# FPGA_Clocks.net
KiCad netlist of a schematic drawn in Altium Designer
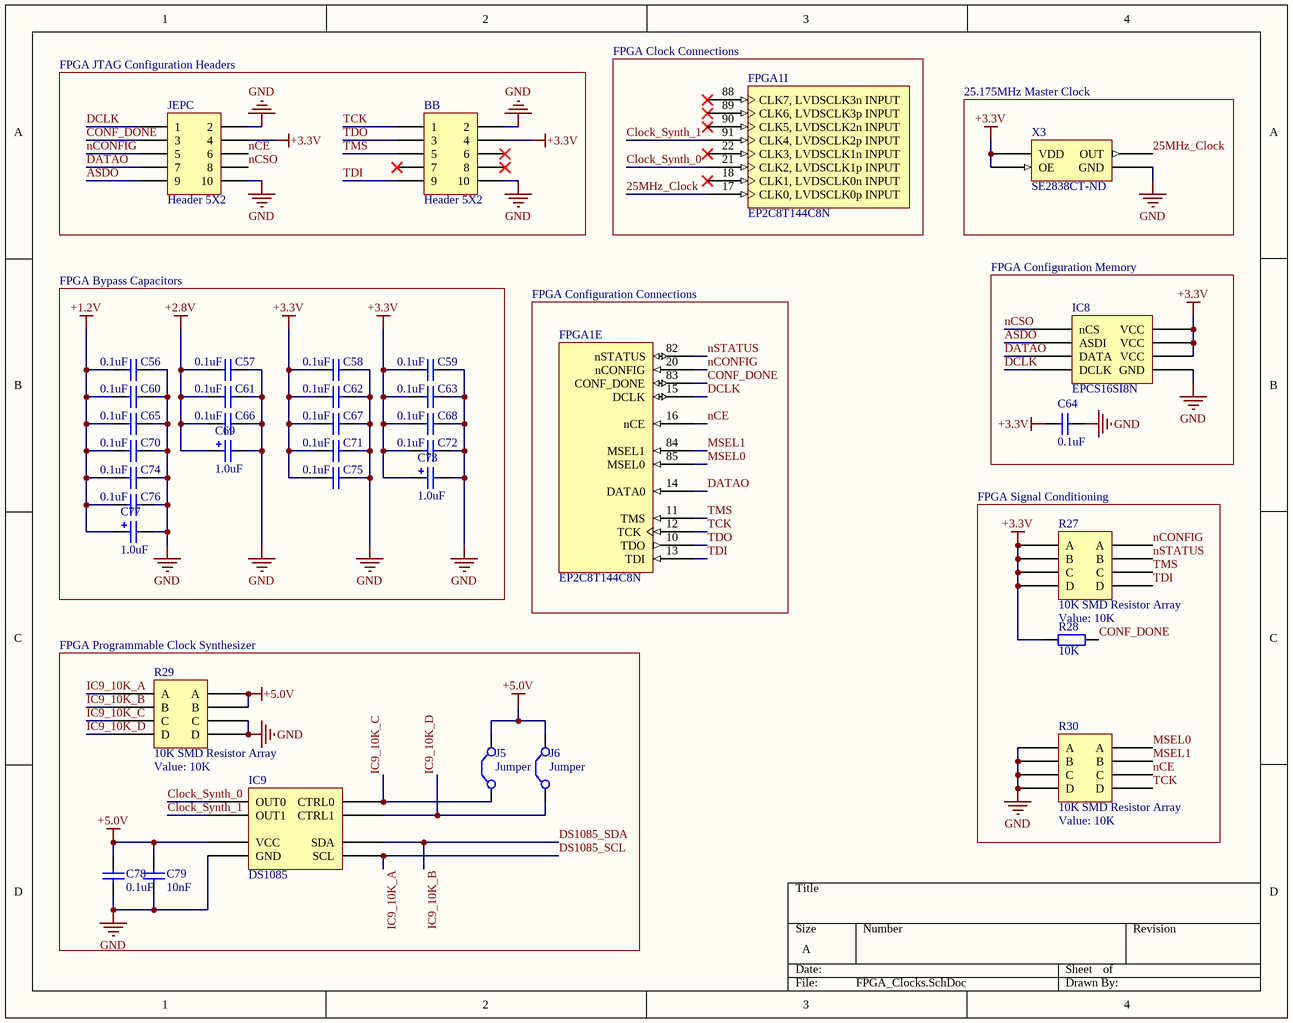
[diagram p0: FPGA_Clocks.SchDoc]

(export (version "E")
  (design (tool "Eeschema 10.0.6"))
  (components
    (comp (ref "BB")
      (value "Header 5X2")
      (footprint "HDR2X5")
      (description "Header, 5-Pin, Dual row")
      (fields (field (name "PUBLISHER") "Altium Limited"))
      (libsource (lib "Miscellaneous Connectors") (part "Header 5X2"))
    )
    (comp (ref "C56")
      (value "0.1uF")
      (footprint "SMD 1206")
      (description "Capacitor")
      (fields (field (name "Comment") "0.1uF SMD 1206"))
      (libsource (lib "Miscellaneous Devices") (part "Cap"))
    )
    (comp (ref "C57")
      (value "0.1uF")
      (footprint "SMD 1206")
      (description "Capacitor")
      (fields (field (name "Comment") "0.1uF SMD 1206"))
      (libsource (lib "Miscellaneous Devices") (part "Cap"))
    )
    (comp (ref "C58")
      (value "0.1uF")
      (footprint "SMD 1206")
      (description "Capacitor")
      (fields (field (name "Comment") "0.1uF SMD 1206"))
      (libsource (lib "Miscellaneous Devices") (part "Cap"))
    )
    (comp (ref "C59")
      (value "0.1uF")
      (footprint "SMD 1206")
      (description "Capacitor")
      (fields (field (name "Comment") "0.1uF SMD 1206"))
      (libsource (lib "Miscellaneous Devices") (part "Cap"))
    )
    (comp (ref "C60")
      (value "0.1uF")
      (footprint "SMD 1206")
      (description "Capacitor")
      (fields (field (name "Comment") "0.1uF SMD 1206"))
      (libsource (lib "Miscellaneous Devices") (part "Cap"))
    )
    (comp (ref "C61")
      (value "0.1uF")
      (footprint "SMD 1206")
      (description "Capacitor")
      (fields (field (name "Comment") "0.1uF SMD 1206"))
      (libsource (lib "Miscellaneous Devices") (part "Cap"))
    )
    (comp (ref "C62")
      (value "0.1uF")
      (footprint "SMD 1206")
      (description "Capacitor")
      (fields (field (name "Comment") "0.1uF SMD 1206"))
      (libsource (lib "Miscellaneous Devices") (part "Cap"))
    )
    (comp (ref "C63")
      (value "0.1uF")
      (footprint "SMD 1206")
      (description "Capacitor")
      (fields (field (name "Comment") "0.1uF SMD 1206"))
      (libsource (lib "Miscellaneous Devices") (part "Cap"))
    )
    (comp (ref "C64")
      (value "0.1uF")
      (footprint "SMD 1206")
      (description "Capacitor")
      (fields (field (name "Comment") "0.1uF SMD 1206"))
      (libsource (lib "Miscellaneous Devices") (part "Cap"))
    )
    (comp (ref "C65")
      (value "0.1uF")
      (footprint "SMD 1206")
      (description "Capacitor")
      (fields (field (name "Comment") "0.1uF SMD 1206"))
      (libsource (lib "Miscellaneous Devices") (part "Cap"))
    )
    (comp (ref "C66")
      (value "0.1uF")
      (footprint "SMD 1206")
      (description "Capacitor")
      (fields (field (name "Comment") "0.1uF SMD 1206"))
      (libsource (lib "Miscellaneous Devices") (part "Cap"))
    )
    (comp (ref "C67")
      (value "0.1uF")
      (footprint "SMD 1206")
      (description "Capacitor")
      (fields (field (name "Comment") "0.1uF SMD 1206"))
      (libsource (lib "Miscellaneous Devices") (part "Cap"))
    )
    (comp (ref "C68")
      (value "0.1uF")
      (footprint "SMD 1206")
      (description "Capacitor")
      (fields (field (name "Comment") "0.1uF SMD 1206"))
      (libsource (lib "Miscellaneous Devices") (part "Cap"))
    )
    (comp (ref "C69")
      (value "1.0uF")
      (footprint "Capacitor - Tantalum Case A")
      (description "Tantalum Capacitor - Case A")
      (fields (field (name "Comment") "1.0uF Low-ESR Tantalum CaseA"))
      (libsource (lib "Ad-Flier_Parts") (part "SMD_Cap_Tantalum"))
    )
    (comp (ref "C70")
      (value "0.1uF")
      (footprint "SMD 1206")
      (description "Capacitor")
      (fields (field (name "Comment") "0.1uF SMD 1206"))
      (libsource (lib "Miscellaneous Devices") (part "Cap"))
    )
    (comp (ref "C71")
      (value "0.1uF")
      (footprint "SMD 1206")
      (description "Capacitor")
      (fields (field (name "Comment") "0.1uF SMD 1206"))
      (libsource (lib "Miscellaneous Devices") (part "Cap"))
    )
    (comp (ref "C72")
      (value "0.1uF")
      (footprint "SMD 1206")
      (description "Capacitor")
      (fields (field (name "Comment") "0.1uF SMD 1206"))
      (libsource (lib "Miscellaneous Devices") (part "Cap"))
    )
    (comp (ref "C73")
      (value "1.0uF")
      (footprint "Capacitor - Tantalum Case A")
      (description "Tantalum Capacitor - Case A")
      (fields (field (name "Comment") "1.0uF Low-ESR Tantalum CaseA"))
      (libsource (lib "Ad-Flier_Parts") (part "SMD_Cap_Tantalum"))
    )
    (comp (ref "C74")
      (value "0.1uF")
      (footprint "SMD 1206")
      (description "Capacitor")
      (fields (field (name "Comment") "0.1uF SMD 1206"))
      (libsource (lib "Miscellaneous Devices") (part "Cap"))
    )
    (comp (ref "C75")
      (value "0.1uF")
      (footprint "SMD 1206")
      (description "Capacitor")
      (fields (field (name "Comment") "0.1uF SMD 1206"))
      (libsource (lib "Miscellaneous Devices") (part "Cap"))
    )
    (comp (ref "C76")
      (value "0.1uF")
      (footprint "SMD 1206")
      (description "Capacitor")
      (fields (field (name "Comment") "0.1uF SMD 1206"))
      (libsource (lib "Miscellaneous Devices") (part "Cap"))
    )
    (comp (ref "C77")
      (value "1.0uF")
      (footprint "Capacitor - Tantalum Case A")
      (description "Tantalum Capacitor - Case A")
      (fields (field (name "Comment") "1.0uF Low-ESR Tantalum CaseA"))
      (libsource (lib "Ad-Flier_Parts") (part "SMD_Cap_Tantalum"))
    )
    (comp (ref "C78")
      (value "0.1uF")
      (footprint "SMD 1206")
      (description "Capacitor")
      (fields (field (name "Comment") "0.1uF SMD 1206"))
      (libsource (lib "Miscellaneous Devices") (part "Cap"))
    )
    (comp (ref "C79")
      (value "10nF")
      (footprint "SMD 1206")
      (description "Capacitor")
      (fields (field (name "Comment") "10nF SMD 1206"))
      (libsource (lib "Miscellaneous Devices") (part "Cap"))
    )
    (comp (ref "FPGA1")
      (value "EP2C8T144C8N")
      (footprint "TQFP144_N")
      (fields (field (name "PUBLISHER") "Altium Limited"))
      (libsource (lib "") (part "EP2C8T144C8N_1"))
    )
    (comp (ref "IC8")
      (value "EPCS16SI8N")
      (footprint "EPCS16SI8N SO-8")
      (description "16MB FPGA CONFIGURATION DEVICE")
      (libsource (lib "Ad-Flier_Parts") (part "EPCS16SI8N"))
    )
    (comp (ref "IC9")
      (value "DS1085")
      (footprint "DS1085 SO-150mil")
      (description "EconOscillator Frequency Synthesizer")
      (libsource (lib "Ad-Flier_Parts") (part "DS1085"))
    )
    (comp (ref "J5")
      (value "Jumper")
      (footprint "HDR1X2")
      (description "Jumper Wire")
      (fields (field (name "PUBLISHER") "Altium Limited"))
      (libsource (lib "Miscellaneous Devices") (part "Jumper"))
    )
    (comp (ref "J6")
      (value "Jumper")
      (footprint "HDR1X2")
      (description "Jumper Wire")
      (fields (field (name "PUBLISHER") "Altium Limited"))
      (libsource (lib "Miscellaneous Devices") (part "Jumper"))
    )
    (comp (ref "JEPC")
      (value "Header 5X2")
      (footprint "HDR2X5")
      (description "Header, 5-Pin, Dual row")
      (fields (field (name "PUBLISHER") "Altium Limited"))
      (libsource (lib "Miscellaneous Connectors") (part "Header 5X2"))
    )
    (comp (ref "R27")
      (value "10K SMD Resistor Array")
      (footprint "Resistor Array YC164")
      (description "4-Count Resistor Array")
      (fields (field (name "ALTIUM_VALUE") "10K"))
      (libsource (lib "Ad-Flier_Parts") (part "SMD Resistor Array"))
    )
    (comp (ref "R28")
      (value "10K")
      (footprint "SMD 0805")
      (description "Resistor")
      (fields (field (name "Comment") "10K SMD 0805"))
      (libsource (lib "Miscellaneous Devices") (part "Res2"))
    )
    (comp (ref "R29")
      (value "10K SMD Resistor Array")
      (footprint "Resistor Array YC164")
      (description "4-Count Resistor Array")
      (fields (field (name "ALTIUM_VALUE") "10K"))
      (libsource (lib "Ad-Flier_Parts") (part "SMD Resistor Array"))
    )
    (comp (ref "R30")
      (value "10K SMD Resistor Array")
      (footprint "Resistor Array YC164")
      (description "4-Count Resistor Array")
      (fields (field (name "ALTIUM_VALUE") "10K"))
      (libsource (lib "Ad-Flier_Parts") (part "SMD Resistor Array"))
    )
    (comp (ref "X3")
      (value "SE2838CT-ND")
      (footprint "SG-636PCE 25.175MHz Crystal")
      (description "OSCILLATOR 25.1750MHZ SMD")
      (libsource (lib "Ad-Flier_Parts") (part "SE2838CT-ND"))
    )
  )
  (nets
    (net (code "1") (name "+1.2V") (class "Default")
      (node (ref "C56") (pin "1") (pinfunction "1_1") (pintype "passive"))
      (node (ref "C60") (pin "1") (pinfunction "1_1") (pintype "passive"))
      (node (ref "C65") (pin "1") (pinfunction "1_1") (pintype "passive"))
      (node (ref "C70") (pin "1") (pinfunction "1_1") (pintype "passive"))
      (node (ref "C74") (pin "1") (pinfunction "1_1") (pintype "passive"))
      (node (ref "C76") (pin "1") (pinfunction "1_1") (pintype "passive"))
      (node (ref "C77") (pin "1") (pinfunction "+_1") (pintype "passive"))
    )
    (net (code "2") (name "+2.8V") (class "Default")
      (node (ref "C57") (pin "1") (pinfunction "1_1") (pintype "passive"))
      (node (ref "C61") (pin "1") (pinfunction "1_1") (pintype "passive"))
      (node (ref "C66") (pin "1") (pinfunction "1_1") (pintype "passive"))
      (node (ref "C69") (pin "1") (pinfunction "+_1") (pintype "passive"))
    )
    (net (code "3") (name "+3.3V") (class "Default")
      (node (ref "BB") (pin "4") (pinfunction "4_4") (pintype "passive"))
      (node (ref "C58") (pin "1") (pinfunction "1_1") (pintype "passive"))
      (node (ref "C59") (pin "1") (pinfunction "1_1") (pintype "passive"))
      (node (ref "C62") (pin "1") (pinfunction "1_1") (pintype "passive"))
      (node (ref "C63") (pin "1") (pinfunction "1_1") (pintype "passive"))
      (node (ref "C64") (pin "1") (pinfunction "1_1") (pintype "passive"))
      (node (ref "C67") (pin "1") (pinfunction "1_1") (pintype "passive"))
      (node (ref "C68") (pin "1") (pinfunction "1_1") (pintype "passive"))
      (node (ref "C71") (pin "1") (pinfunction "1_1") (pintype "passive"))
      (node (ref "C72") (pin "1") (pinfunction "1_1") (pintype "passive"))
      (node (ref "C73") (pin "1") (pinfunction "+_1") (pintype "passive"))
      (node (ref "C75") (pin "1") (pinfunction "1_1") (pintype "passive"))
      (node (ref "IC8") (pin "2") (pinfunction "VCC_2") (pintype "power_in"))
      (node (ref "IC8") (pin "6") (pinfunction "VCC_6") (pintype "power_in"))
      (node (ref "IC8") (pin "7") (pinfunction "VCC_7") (pintype "power_in"))
      (node (ref "JEPC") (pin "4") (pinfunction "4_4") (pintype "passive"))
      (node (ref "R27") (pin "5") (pinfunction "A_5") (pintype "passive"))
      (node (ref "R27") (pin "6") (pinfunction "B_6") (pintype "passive"))
      (node (ref "R27") (pin "7") (pinfunction "C_7") (pintype "passive"))
      (node (ref "R27") (pin "8") (pinfunction "D_8") (pintype "passive"))
      (node (ref "R28") (pin "1") (pinfunction "1_1") (pintype "passive"))
      (node (ref "X3") (pin "0") (pinfunction "OE_0") (pintype "input"))
      (node (ref "X3") (pin "3") (pinfunction "VDD_3") (pintype "power_in"))
    )
    (net (code "4") (name "+5.0V") (class "Default")
      (node (ref "C78") (pin "2") (pinfunction "2_2") (pintype "passive"))
      (node (ref "C79") (pin "2") (pinfunction "2_2") (pintype "passive"))
      (node (ref "IC9") (pin "2") (pinfunction "VCC_2") (pintype "passive"))
      (node (ref "J5") (pin "2") (pinfunction "C2_2") (pintype "passive"))
      (node (ref "J6") (pin "2") (pinfunction "C2_2") (pintype "passive"))
      (node (ref "R29") (pin "1") (pinfunction "A_1") (pintype "passive"))
      (node (ref "R29") (pin "2") (pinfunction "B_2") (pintype "passive"))
    )
    (net (code "5") (name "/25MHz_Clock") (class "Default")
      (node (ref "FPGA1") (pin "17") (pinfunction "CLK0,_LVDSCLK0p_INPUT_17") (pintype "input"))
      (node (ref "X3") (pin "2") (pinfunction "OUT_2") (pintype "output"))
    )
    (net (code "6") (name "/ASDO") (class "Default")
      (node (ref "IC8") (pin "4") (pinfunction "ASDI_4") (pintype "passive"))
      (node (ref "JEPC") (pin "9") (pinfunction "9_9") (pintype "passive"))
    )
    (net (code "7") (name "/CONF_DONE") (class "Default")
      (node (ref "FPGA1") (pin "83") (pinfunction "CONF_DONE_83") (pintype "bidirectional"))
      (node (ref "JEPC") (pin "3") (pinfunction "3_3") (pintype "passive"))
      (node (ref "R28") (pin "2") (pinfunction "2_2") (pintype "passive"))
    )
    (net (code "8") (name "/Clock_Synth_0") (class "Default")
      (node (ref "FPGA1") (pin "21") (pinfunction "CLK2,_LVDSCLK1p_INPUT_21") (pintype "input"))
      (node (ref "IC9") (pin "1") (pinfunction "OUT0_1") (pintype "passive"))
    )
    (net (code "9") (name "/Clock_Synth_1") (class "Default")
      (node (ref "FPGA1") (pin "91") (pinfunction "CLK4,_LVDSCLK2p_INPUT_91") (pintype "input"))
      (node (ref "IC9") (pin "0") (pinfunction "OUT1_0") (pintype "passive"))
    )
    (net (code "10") (name "/DATAO") (class "Default")
      (node (ref "FPGA1") (pin "14") (pinfunction "DATA0_14") (pintype "input"))
      (node (ref "IC8") (pin "1") (pinfunction "DATA_1") (pintype "passive"))
      (node (ref "JEPC") (pin "7") (pinfunction "7_7") (pintype "passive"))
    )
    (net (code "11") (name "/DCLK") (class "Default")
      (node (ref "FPGA1") (pin "15") (pinfunction "DCLK_15") (pintype "bidirectional"))
      (node (ref "IC8") (pin "5") (pinfunction "DCLK_5") (pintype "passive"))
      (node (ref "JEPC") (pin "1") (pinfunction "1_1") (pintype "passive"))
    )
    (net (code "12") (name "/DS1085_SCL") (class "Default")
      (node (ref "IC9") (pin "7") (pinfunction "SCL_7") (pintype "passive"))
      (node (ref "R29") (pin "5") (pinfunction "A_5") (pintype "passive"))
    )
    (net (code "13") (name "/DS1085_SDA") (class "Default")
      (node (ref "IC9") (pin "6") (pinfunction "SDA_6") (pintype "passive"))
      (node (ref "R29") (pin "6") (pinfunction "B_6") (pintype "passive"))
    )
    (net (code "14") (name "/IC9_10K_C") (class "Default")
      (node (ref "IC9") (pin "4") (pinfunction "CTRL0_4") (pintype "passive"))
      (node (ref "J5") (pin "1") (pinfunction "C1_1") (pintype "passive"))
      (node (ref "R29") (pin "7") (pinfunction "C_7") (pintype "passive"))
    )
    (net (code "15") (name "/IC9_10K_D") (class "Default")
      (node (ref "IC9") (pin "5") (pinfunction "CTRL1_5") (pintype "passive"))
      (node (ref "J6") (pin "1") (pinfunction "C1_1") (pintype "passive"))
      (node (ref "R29") (pin "8") (pinfunction "D_8") (pintype "passive"))
    )
    (net (code "16") (name "/MSEL0") (class "Default")
      (node (ref "FPGA1") (pin "85") (pinfunction "MSEL0_85") (pintype "input"))
      (node (ref "R30") (pin "1") (pinfunction "A_1") (pintype "passive"))
    )
    (net (code "17") (name "/MSEL1") (class "Default")
      (node (ref "FPGA1") (pin "84") (pinfunction "MSEL1_84") (pintype "input"))
      (node (ref "R30") (pin "2") (pinfunction "B_2") (pintype "passive"))
    )
    (net (code "18") (name "/TCK") (class "Default")
      (node (ref "BB") (pin "1") (pinfunction "1_1") (pintype "passive"))
      (node (ref "FPGA1") (pin "12") (pinfunction "TCK_12") (pintype "input"))
      (node (ref "R30") (pin "4") (pinfunction "D_4") (pintype "passive"))
    )
    (net (code "19") (name "/TDI") (class "Default")
      (node (ref "BB") (pin "9") (pinfunction "9_9") (pintype "passive"))
      (node (ref "FPGA1") (pin "13") (pinfunction "TDI_13") (pintype "input"))
      (node (ref "R27") (pin "4") (pinfunction "D_4") (pintype "passive"))
    )
    (net (code "20") (name "/TDO") (class "Default")
      (node (ref "BB") (pin "3") (pinfunction "3_3") (pintype "passive"))
      (node (ref "FPGA1") (pin "10") (pinfunction "TDO_10") (pintype "output"))
    )
    (net (code "21") (name "/TMS") (class "Default")
      (node (ref "BB") (pin "5") (pinfunction "5_5") (pintype "passive"))
      (node (ref "FPGA1") (pin "11") (pinfunction "TMS_11") (pintype "input"))
      (node (ref "R27") (pin "3") (pinfunction "C_3") (pintype "passive"))
    )
    (net (code "22") (name "/nCE") (class "Default")
      (node (ref "FPGA1") (pin "16") (pinfunction "nCE_16") (pintype "input"))
      (node (ref "JEPC") (pin "6") (pinfunction "6_6") (pintype "passive"))
      (node (ref "R30") (pin "3") (pinfunction "C_3") (pintype "passive"))
    )
    (net (code "23") (name "/nCONFIG") (class "Default")
      (node (ref "FPGA1") (pin "20") (pinfunction "nCONFIG_20") (pintype "input"))
      (node (ref "JEPC") (pin "5") (pinfunction "5_5") (pintype "passive"))
      (node (ref "R27") (pin "1") (pinfunction "A_1") (pintype "passive"))
    )
    (net (code "24") (name "/nCSO") (class "Default")
      (node (ref "IC8") (pin "0") (pinfunction "nCS_0") (pintype "passive"))
      (node (ref "JEPC") (pin "8") (pinfunction "8_8") (pintype "passive"))
    )
    (net (code "25") (name "/nSTATUS") (class "Default")
      (node (ref "FPGA1") (pin "82") (pinfunction "nSTATUS_82") (pintype "bidirectional"))
      (node (ref "R27") (pin "2") (pinfunction "B_2") (pintype "passive"))
    )
    (net (code "26") (name "GND") (class "Default")
      (node (ref "BB") (pin "10") (pinfunction "10_10") (pintype "passive"))
      (node (ref "BB") (pin "2") (pinfunction "2_2") (pintype "passive"))
      (node (ref "C56") (pin "2") (pinfunction "2_2") (pintype "passive"))
      (node (ref "C57") (pin "2") (pinfunction "2_2") (pintype "passive"))
      (node (ref "C58") (pin "2") (pinfunction "2_2") (pintype "passive"))
      (node (ref "C59") (pin "2") (pinfunction "2_2") (pintype "passive"))
      (node (ref "C60") (pin "2") (pinfunction "2_2") (pintype "passive"))
      (node (ref "C61") (pin "2") (pinfunction "2_2") (pintype "passive"))
      (node (ref "C62") (pin "2") (pinfunction "2_2") (pintype "passive"))
      (node (ref "C63") (pin "2") (pinfunction "2_2") (pintype "passive"))
      (node (ref "C64") (pin "2") (pinfunction "2_2") (pintype "passive"))
      (node (ref "C65") (pin "2") (pinfunction "2_2") (pintype "passive"))
      (node (ref "C66") (pin "2") (pinfunction "2_2") (pintype "passive"))
      (node (ref "C67") (pin "2") (pinfunction "2_2") (pintype "passive"))
      (node (ref "C68") (pin "2") (pinfunction "2_2") (pintype "passive"))
      (node (ref "C69") (pin "2") (pinfunction "-_2") (pintype "passive"))
      (node (ref "C70") (pin "2") (pinfunction "2_2") (pintype "passive"))
      (node (ref "C71") (pin "2") (pinfunction "2_2") (pintype "passive"))
      (node (ref "C72") (pin "2") (pinfunction "2_2") (pintype "passive"))
      (node (ref "C73") (pin "2") (pinfunction "-_2") (pintype "passive"))
      (node (ref "C74") (pin "2") (pinfunction "2_2") (pintype "passive"))
      (node (ref "C75") (pin "2") (pinfunction "2_2") (pintype "passive"))
      (node (ref "C76") (pin "2") (pinfunction "2_2") (pintype "passive"))
      (node (ref "C77") (pin "2") (pinfunction "-_2") (pintype "passive"))
      (node (ref "C78") (pin "1") (pinfunction "1_1") (pintype "passive"))
      (node (ref "C79") (pin "1") (pinfunction "1_1") (pintype "passive"))
      (node (ref "IC8") (pin "3") (pinfunction "GND_3") (pintype "power_in"))
      (node (ref "IC9") (pin "3") (pinfunction "GND_3") (pintype "passive"))
      (node (ref "JEPC") (pin "10") (pinfunction "10_10") (pintype "passive"))
      (node (ref "JEPC") (pin "2") (pinfunction "2_2") (pintype "passive"))
      (node (ref "R29") (pin "3") (pinfunction "C_3") (pintype "passive"))
      (node (ref "R29") (pin "4") (pinfunction "D_4") (pintype "passive"))
      (node (ref "R30") (pin "5") (pinfunction "A_5") (pintype "passive"))
      (node (ref "R30") (pin "6") (pinfunction "B_6") (pintype "passive"))
      (node (ref "R30") (pin "7") (pinfunction "C_7") (pintype "passive"))
      (node (ref "R30") (pin "8") (pinfunction "D_8") (pintype "passive"))
      (node (ref "X3") (pin "1") (pinfunction "GND_1") (pintype "power_in"))
    )
    (net (code "27") (name "unconnected-(BB-Pad6)") (class "Default")
      (node (ref "BB") (pin "6") (pinfunction "6_6") (pintype "passive+no_connect"))
    )
    (net (code "28") (name "unconnected-(BB-Pad7)") (class "Default")
      (node (ref "BB") (pin "7") (pinfunction "7_7") (pintype "passive+no_connect"))
    )
    (net (code "29") (name "unconnected-(BB-Pad8)") (class "Default")
      (node (ref "BB") (pin "8") (pinfunction "8_8") (pintype "passive+no_connect"))
    )
    (net (code "30") (name "unconnected-(FPGA1I-CLK1,_LVDSCLK0n_INPUT-Pad18)") (class "Default")
      (node (ref "FPGA1") (pin "18") (pinfunction "CLK1,_LVDSCLK0n_INPUT_18") (pintype "input+no_connect"))
    )
    (net (code "31") (name "unconnected-(FPGA1I-CLK3,_LVDSCLK1n_INPUT-Pad22)") (class "Default")
      (node (ref "FPGA1") (pin "22") (pinfunction "CLK3,_LVDSCLK1n_INPUT_22") (pintype "input+no_connect"))
    )
    (net (code "32") (name "unconnected-(FPGA1I-CLK5,_LVDSCLK2n_INPUT-Pad90)") (class "Default")
      (node (ref "FPGA1") (pin "90") (pinfunction "CLK5,_LVDSCLK2n_INPUT_90") (pintype "input+no_connect"))
    )
    (net (code "33") (name "unconnected-(FPGA1I-CLK6,_LVDSCLK3p_INPUT-Pad89)") (class "Default")
      (node (ref "FPGA1") (pin "89") (pinfunction "CLK6,_LVDSCLK3p_INPUT_89") (pintype "input+no_connect"))
    )
    (net (code "34") (name "unconnected-(FPGA1I-CLK7,_LVDSCLK3n_INPUT-Pad88)") (class "Default")
      (node (ref "FPGA1") (pin "88") (pinfunction "CLK7,_LVDSCLK3n_INPUT_88") (pintype "input+no_connect"))
    )
  )
)
